# 24V_RAIL.net
KiCad netlist of a schematic drawn in EAGLE
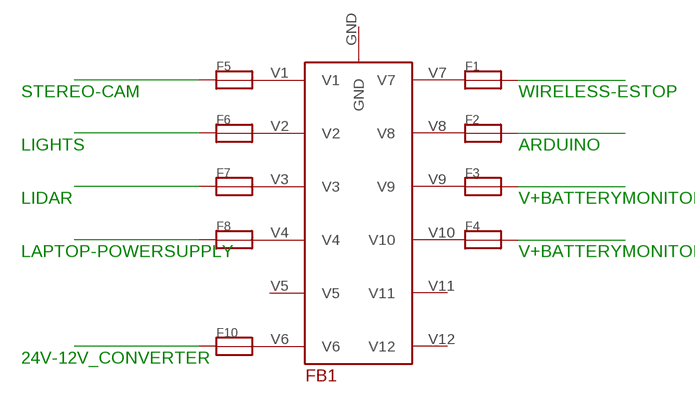
[diagram p0: schematic, sheet 1]

(export (version "E")
  (design (tool "Eeschema 10.0.6"))
  (components
    (comp (ref "F1")
      (value "FUSE")
      (footprint "eagle-import:FUSE")
      (libsource (lib "eagle-import") (part "FUSE"))
    )
    (comp (ref "F2")
      (value "FUSE")
      (footprint "eagle-import:FUSE")
      (libsource (lib "eagle-import") (part "FUSE"))
    )
    (comp (ref "F3")
      (value "FUSE")
      (footprint "eagle-import:FUSE")
      (libsource (lib "eagle-import") (part "FUSE"))
    )
    (comp (ref "F4")
      (value "FUSE")
      (footprint "eagle-import:FUSE")
      (libsource (lib "eagle-import") (part "FUSE"))
    )
    (comp (ref "F5")
      (value "FUSE")
      (footprint "eagle-import:FUSE")
      (libsource (lib "eagle-import") (part "FUSE"))
    )
    (comp (ref "F6")
      (value "FUSE")
      (footprint "eagle-import:FUSE")
      (libsource (lib "eagle-import") (part "FUSE"))
    )
    (comp (ref "F7")
      (value "FUSE")
      (footprint "eagle-import:FUSE")
      (libsource (lib "eagle-import") (part "FUSE"))
    )
    (comp (ref "F8")
      (value "FUSE")
      (footprint "eagle-import:FUSE")
      (libsource (lib "eagle-import") (part "FUSE"))
    )
    (comp (ref "F10")
      (value "FUSE")
      (footprint "eagle-import:FUSE")
      (libsource (lib "eagle-import") (part "FUSE"))
    )
    (comp (ref "FB1")
      (value "FUSEBLOCK-12")
      (footprint "eagle-import:FUSEBLOCK-12PT")
      (libsource (lib "eagle-import") (part "FUSEBLOCK-12"))
    )
  )
  (nets
    (net (code "1") (name "/GND") (class "Default")
      (node (ref "FB1") (pin "GND") (pinfunction "GND_GND") (pintype "power_in"))
    )
    (net (code "2") (name "/V5") (class "Default")
      (node (ref "FB1") (pin "V5") (pinfunction "V5_V5") (pintype "power_in"))
    )
    (net (code "3") (name "/V11") (class "Default")
      (node (ref "FB1") (pin "V11") (pinfunction "V11_V11") (pintype "power_in"))
    )
    (net (code "4") (name "/V12") (class "Default")
      (node (ref "FB1") (pin "V12") (pinfunction "V12_V12") (pintype "power_in"))
    )
    (net (code "5") (name "Net-(F1-PadP$1)") (class "Default")
      (node (ref "F1") (pin "P$1") (pinfunction "P$1_P$1") (pintype "bidirectional"))
      (node (ref "FB1") (pin "V7") (pinfunction "V7_V7") (pintype "power_in"))
    )
    (net (code "6") (name "Net-(F2-PadP$1)") (class "Default")
      (node (ref "F2") (pin "P$1") (pinfunction "P$1_P$1") (pintype "bidirectional"))
      (node (ref "FB1") (pin "V8") (pinfunction "V8_V8") (pintype "power_in"))
    )
    (net (code "7") (name "Net-(F3-PadP$1)") (class "Default")
      (node (ref "F3") (pin "P$1") (pinfunction "P$1_P$1") (pintype "bidirectional"))
      (node (ref "FB1") (pin "V9") (pinfunction "V9_V9") (pintype "power_in"))
    )
    (net (code "8") (name "Net-(F4-PadP$1)") (class "Default")
      (node (ref "F4") (pin "P$1") (pinfunction "P$1_P$1") (pintype "bidirectional"))
      (node (ref "FB1") (pin "V10") (pinfunction "V10_V10") (pintype "power_in"))
    )
    (net (code "9") (name "Net-(F5-PadP$2)") (class "Default")
      (node (ref "F5") (pin "P$2") (pinfunction "P$2_P$2") (pintype "bidirectional"))
      (node (ref "FB1") (pin "V1") (pinfunction "V1_V1") (pintype "power_in"))
    )
    (net (code "10") (name "Net-(F6-PadP$2)") (class "Default")
      (node (ref "F6") (pin "P$2") (pinfunction "P$2_P$2") (pintype "bidirectional"))
      (node (ref "FB1") (pin "V2") (pinfunction "V2_V2") (pintype "power_in"))
    )
    (net (code "11") (name "Net-(F7-PadP$2)") (class "Default")
      (node (ref "F7") (pin "P$2") (pinfunction "P$2_P$2") (pintype "bidirectional"))
      (node (ref "FB1") (pin "V3") (pinfunction "V3_V3") (pintype "power_in"))
    )
    (net (code "12") (name "Net-(F8-PadP$2)") (class "Default")
      (node (ref "F8") (pin "P$2") (pinfunction "P$2_P$2") (pintype "bidirectional"))
      (node (ref "FB1") (pin "V4") (pinfunction "V4_V4") (pintype "power_in"))
    )
    (net (code "13") (name "Net-(F10-PadP$2)") (class "Default")
      (node (ref "F10") (pin "P$2") (pinfunction "P$2_P$2") (pintype "bidirectional"))
      (node (ref "FB1") (pin "V6") (pinfunction "V6_V6") (pintype "power_in"))
    )
    (net (code "14") (name "unconnected-(F1-PadP$2)") (class "Default")
      (node (ref "F1") (pin "P$2") (pinfunction "P$2_P$2") (pintype "bidirectional"))
    )
    (net (code "15") (name "unconnected-(F2-PadP$2)") (class "Default")
      (node (ref "F2") (pin "P$2") (pinfunction "P$2_P$2") (pintype "bidirectional"))
    )
    (net (code "16") (name "unconnected-(F3-PadP$2)") (class "Default")
      (node (ref "F3") (pin "P$2") (pinfunction "P$2_P$2") (pintype "bidirectional"))
    )
    (net (code "17") (name "unconnected-(F4-PadP$2)") (class "Default")
      (node (ref "F4") (pin "P$2") (pinfunction "P$2_P$2") (pintype "bidirectional"))
    )
    (net (code "18") (name "unconnected-(F5-PadP$1)") (class "Default")
      (node (ref "F5") (pin "P$1") (pinfunction "P$1_P$1") (pintype "bidirectional"))
    )
    (net (code "19") (name "unconnected-(F6-PadP$1)") (class "Default")
      (node (ref "F6") (pin "P$1") (pinfunction "P$1_P$1") (pintype "bidirectional"))
    )
    (net (code "20") (name "unconnected-(F7-PadP$1)") (class "Default")
      (node (ref "F7") (pin "P$1") (pinfunction "P$1_P$1") (pintype "bidirectional"))
    )
    (net (code "21") (name "unconnected-(F8-PadP$1)") (class "Default")
      (node (ref "F8") (pin "P$1") (pinfunction "P$1_P$1") (pintype "bidirectional"))
    )
    (net (code "22") (name "unconnected-(F10-PadP$1)") (class "Default")
      (node (ref "F10") (pin "P$1") (pinfunction "P$1_P$1") (pintype "bidirectional"))
    )
  )
)
